# Support.net
KiCad netlist of a schematic drawn in Altium Designer
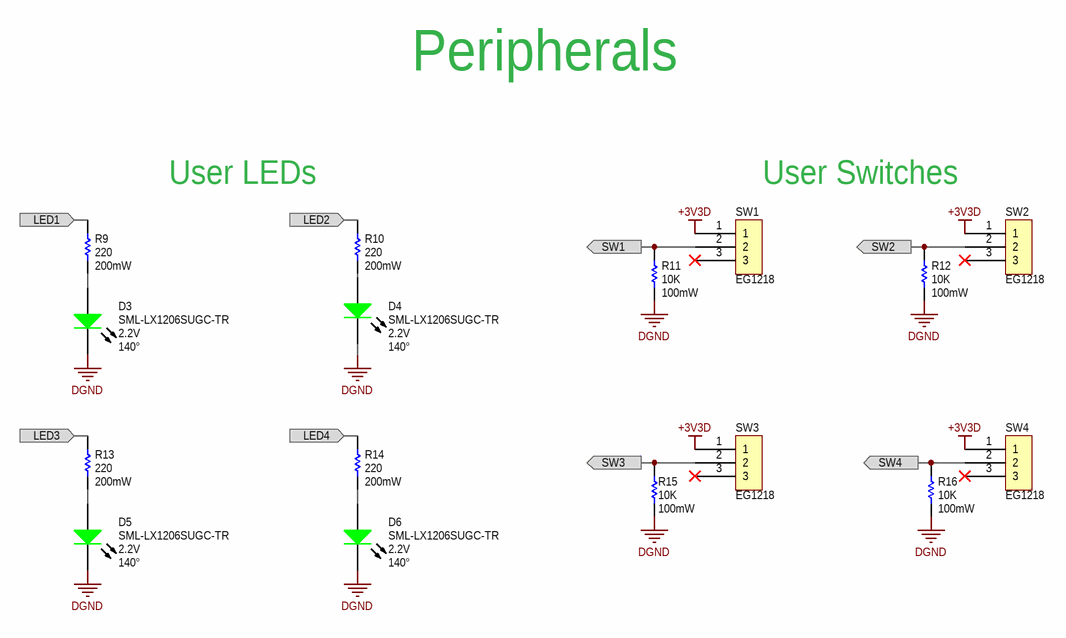
[diagram p0: Support.SchDoc]

(export (version "E")
  (design (tool "Eeschema 10.0.6"))
  (components
    (comp (ref "D3")
      (value "LED_GREEN 2")
      (footprint "DIOCP3216X11L")
      (description "LED ALINGAP ULT GRN CLR 1206 SMD")
      (fields
        (field (name "MANUFACTURER") "Lumex Opto/Components Inc")
        (field (name "MANUFACTURER PART NUMBER") "SML-LX1206SUGC-TR")
        (field (name "VOLTAGE - FORWARD (VF) TYP") "2.2V")
        (field (name "VIEWING ANGLE") "140°")
      )
      (libsource (lib "Schematic_Components") (part "LED_GREEN 2"))
    )
    (comp (ref "D4")
      (value "LED_GREEN 2")
      (footprint "DIOCP3216X11L")
      (description "LED ALINGAP ULT GRN CLR 1206 SMD")
      (fields
        (field (name "MANUFACTURER") "Lumex Opto/Components Inc")
        (field (name "MANUFACTURER PART NUMBER") "SML-LX1206SUGC-TR")
        (field (name "VOLTAGE - FORWARD (VF) TYP") "2.2V")
        (field (name "VIEWING ANGLE") "140°")
      )
      (libsource (lib "Schematic_Components") (part "LED_GREEN 2"))
    )
    (comp (ref "D5")
      (value "LED_GREEN 2")
      (footprint "DIOCP3216X11L")
      (description "LED ALINGAP ULT GRN CLR 1206 SMD")
      (fields
        (field (name "MANUFACTURER") "Lumex Opto/Components Inc")
        (field (name "MANUFACTURER PART NUMBER") "SML-LX1206SUGC-TR")
        (field (name "VOLTAGE - FORWARD (VF) TYP") "2.2V")
        (field (name "VIEWING ANGLE") "140°")
      )
      (libsource (lib "Schematic_Components") (part "LED_GREEN 2"))
    )
    (comp (ref "D6")
      (value "LED_GREEN 2")
      (footprint "DIOCP3216X11L")
      (description "LED ALINGAP ULT GRN CLR 1206 SMD")
      (fields
        (field (name "MANUFACTURER") "Lumex Opto/Components Inc")
        (field (name "MANUFACTURER PART NUMBER") "SML-LX1206SUGC-TR")
        (field (name "VOLTAGE - FORWARD (VF) TYP") "2.2V")
        (field (name "VIEWING ANGLE") "140°")
      )
      (libsource (lib "Schematic_Components") (part "LED_GREEN 2"))
    )
    (comp (ref "R9")
      (value "ERJ-PB3B2200V")
      (footprint "3-0603_R_L")
      (description "RES SMD 220 OHM 0.1% 1/5W 0603")
      (fields
        (field (name "MANUFACTURER") "Panasonic Electronic Components")
        (field (name "TOLERANCE") "±0.1%")
        (field (name "POWER (WATTS)") "200mW")
        (field (name "RESISTANCE (OHMS)") "220")
      )
      (libsource (lib "Schematic_Components_CD") (part "ERJ-PB3B2200V"))
    )
    (comp (ref "R10")
      (value "ERJ-PB3B2200V")
      (footprint "3-0603_R_L")
      (description "RES SMD 220 OHM 0.1% 1/5W 0603")
      (fields
        (field (name "MANUFACTURER") "Panasonic Electronic Components")
        (field (name "TOLERANCE") "±0.1%")
        (field (name "POWER (WATTS)") "200mW")
        (field (name "RESISTANCE (OHMS)") "220")
      )
      (libsource (lib "Schematic_Components_CD") (part "ERJ-PB3B2200V"))
    )
    (comp (ref "R11")
      (value "ERJ-3GEYJ103V")
      (footprint "3-0603_R_L")
      (description "RES 10K OHM 1/10W 5% 0603 SMD")
      (fields
        (field (name "MANUFACTURER") "Panasonic - ECG")
        (field (name "POWER (WATTS)") "100mW")
        (field (name "TOLERANCE") "±5%")
        (field (name "RESISTANCE (OHMS)") "10K")
      )
      (libsource (lib "Schematic_Components") (part "ERJ-3GEYJ103V"))
    )
    (comp (ref "R12")
      (value "ERJ-3GEYJ103V")
      (footprint "3-0603_R_L")
      (description "RES 10K OHM 1/10W 5% 0603 SMD")
      (fields
        (field (name "MANUFACTURER") "Panasonic - ECG")
        (field (name "POWER (WATTS)") "100mW")
        (field (name "TOLERANCE") "±5%")
        (field (name "RESISTANCE (OHMS)") "10K")
      )
      (libsource (lib "Schematic_Components") (part "ERJ-3GEYJ103V"))
    )
    (comp (ref "R13")
      (value "ERJ-PB3B2200V")
      (footprint "3-0603_R_L")
      (description "RES SMD 220 OHM 0.1% 1/5W 0603")
      (fields
        (field (name "MANUFACTURER") "Panasonic Electronic Components")
        (field (name "TOLERANCE") "±0.1%")
        (field (name "POWER (WATTS)") "200mW")
        (field (name "RESISTANCE (OHMS)") "220")
      )
      (libsource (lib "Schematic_Components_CD") (part "ERJ-PB3B2200V"))
    )
    (comp (ref "R14")
      (value "ERJ-PB3B2200V")
      (footprint "3-0603_R_L")
      (description "RES SMD 220 OHM 0.1% 1/5W 0603")
      (fields
        (field (name "MANUFACTURER") "Panasonic Electronic Components")
        (field (name "TOLERANCE") "±0.1%")
        (field (name "POWER (WATTS)") "200mW")
        (field (name "RESISTANCE (OHMS)") "220")
      )
      (libsource (lib "Schematic_Components_CD") (part "ERJ-PB3B2200V"))
    )
    (comp (ref "R15")
      (value "ERJ-3GEYJ103V")
      (footprint "3-0603_R_L")
      (description "RES 10K OHM 1/10W 5% 0603 SMD")
      (fields
        (field (name "MANUFACTURER") "Panasonic - ECG")
        (field (name "POWER (WATTS)") "100mW")
        (field (name "TOLERANCE") "±5%")
        (field (name "RESISTANCE (OHMS)") "10K")
      )
      (libsource (lib "Schematic_Components") (part "ERJ-3GEYJ103V"))
    )
    (comp (ref "R16")
      (value "ERJ-3GEYJ103V")
      (footprint "3-0603_R_L")
      (description "RES 10K OHM 1/10W 5% 0603 SMD")
      (fields
        (field (name "MANUFACTURER") "Panasonic - ECG")
        (field (name "POWER (WATTS)") "100mW")
        (field (name "TOLERANCE") "±5%")
        (field (name "RESISTANCE (OHMS)") "10K")
      )
      (libsource (lib "Schematic_Components") (part "ERJ-3GEYJ103V"))
    )
    (comp (ref "SW1")
      (value "Slide Switch SPDT Through Hole")
      (footprint "EG1218")
      (fields
        (field (name "MANUFACTURER") "E-Switch")
        (field (name "MANUFACTURER PART NUMBER") "EG1218")
        (field (name "PUBLISHER") "Altium Limited")
      )
      (libsource (lib "NIH_DE0_Nano_Daughter_Card_Library") (part "EG1218"))
    )
    (comp (ref "SW2")
      (value "Slide Switch SPDT Through Hole")
      (footprint "EG1218")
      (fields
        (field (name "MANUFACTURER") "E-Switch")
        (field (name "MANUFACTURER PART NUMBER") "EG1218")
        (field (name "PUBLISHER") "Altium Limited")
      )
      (libsource (lib "NIH_DE0_Nano_Daughter_Card_Library") (part "EG1218"))
    )
    (comp (ref "SW3")
      (value "Slide Switch SPDT Through Hole")
      (footprint "EG1218")
      (fields
        (field (name "MANUFACTURER") "E-Switch")
        (field (name "MANUFACTURER PART NUMBER") "EG1218")
        (field (name "PUBLISHER") "Altium Limited")
      )
      (libsource (lib "NIH_DE0_Nano_Daughter_Card_Library") (part "EG1218"))
    )
    (comp (ref "SW4")
      (value "Slide Switch SPDT Through Hole")
      (footprint "EG1218")
      (fields
        (field (name "MANUFACTURER") "E-Switch")
        (field (name "MANUFACTURER PART NUMBER") "EG1218")
        (field (name "PUBLISHER") "Altium Limited")
      )
      (libsource (lib "NIH_DE0_Nano_Daughter_Card_Library") (part "EG1218"))
    )
  )
  (nets
    (net (code "1") (name "+3V3D") (class "Default")
      (node (ref "SW1") (pin "1") (pinfunction "1_1") (pintype "passive"))
      (node (ref "SW2") (pin "1") (pinfunction "1_1") (pintype "passive"))
      (node (ref "SW3") (pin "1") (pinfunction "1_1") (pintype "passive"))
      (node (ref "SW4") (pin "1") (pinfunction "1_1") (pintype "passive"))
    )
    (net (code "2") (name "/LED1") (class "Default")
      (node (ref "R9") (pin "2") (pinfunction "2_2") (pintype "passive"))
    )
    (net (code "3") (name "/LED2") (class "Default")
      (node (ref "R10") (pin "2") (pinfunction "2_2") (pintype "passive"))
    )
    (net (code "4") (name "/LED3") (class "Default")
      (node (ref "R13") (pin "2") (pinfunction "2_2") (pintype "passive"))
    )
    (net (code "5") (name "/LED4") (class "Default")
      (node (ref "R14") (pin "2") (pinfunction "2_2") (pintype "passive"))
    )
    (net (code "6") (name "/SW1") (class "Default")
      (node (ref "R11") (pin "1") (pinfunction "1_1") (pintype "passive"))
      (node (ref "SW1") (pin "2") (pinfunction "2_2") (pintype "passive"))
    )
    (net (code "7") (name "/SW2") (class "Default")
      (node (ref "R12") (pin "1") (pinfunction "1_1") (pintype "passive"))
      (node (ref "SW2") (pin "2") (pinfunction "2_2") (pintype "passive"))
    )
    (net (code "8") (name "/SW3") (class "Default")
      (node (ref "R15") (pin "1") (pinfunction "1_1") (pintype "passive"))
      (node (ref "SW3") (pin "2") (pinfunction "2_2") (pintype "passive"))
    )
    (net (code "9") (name "/SW4") (class "Default")
      (node (ref "R16") (pin "1") (pinfunction "1_1") (pintype "passive"))
      (node (ref "SW4") (pin "2") (pinfunction "2_2") (pintype "passive"))
    )
    (net (code "10") (name "DGND") (class "Default")
      (node (ref "D3") (pin "2") (pinfunction "K_2") (pintype "passive"))
      (node (ref "D4") (pin "2") (pinfunction "K_2") (pintype "passive"))
      (node (ref "D5") (pin "2") (pinfunction "K_2") (pintype "passive"))
      (node (ref "D6") (pin "2") (pinfunction "K_2") (pintype "passive"))
      (node (ref "R11") (pin "2") (pinfunction "2_2") (pintype "passive"))
      (node (ref "R12") (pin "2") (pinfunction "2_2") (pintype "passive"))
      (node (ref "R15") (pin "2") (pinfunction "2_2") (pintype "passive"))
      (node (ref "R16") (pin "2") (pinfunction "2_2") (pintype "passive"))
    )
    (net (code "11") (name "Net-(D3-A)") (class "Default")
      (node (ref "D3") (pin "1") (pinfunction "A_1") (pintype "passive"))
      (node (ref "R9") (pin "1") (pinfunction "1_1") (pintype "passive"))
    )
    (net (code "12") (name "Net-(D4-A)") (class "Default")
      (node (ref "D4") (pin "1") (pinfunction "A_1") (pintype "passive"))
      (node (ref "R10") (pin "1") (pinfunction "1_1") (pintype "passive"))
    )
    (net (code "13") (name "Net-(D5-A)") (class "Default")
      (node (ref "D5") (pin "1") (pinfunction "A_1") (pintype "passive"))
      (node (ref "R13") (pin "1") (pinfunction "1_1") (pintype "passive"))
    )
    (net (code "14") (name "Net-(D6-A)") (class "Default")
      (node (ref "D6") (pin "1") (pinfunction "A_1") (pintype "passive"))
      (node (ref "R14") (pin "1") (pinfunction "1_1") (pintype "passive"))
    )
    (net (code "15") (name "unconnected-(SW1-Pad3)") (class "Default")
      (node (ref "SW1") (pin "3") (pinfunction "3_3") (pintype "passive+no_connect"))
    )
    (net (code "16") (name "unconnected-(SW2-Pad3)") (class "Default")
      (node (ref "SW2") (pin "3") (pinfunction "3_3") (pintype "passive+no_connect"))
    )
    (net (code "17") (name "unconnected-(SW3-Pad3)") (class "Default")
      (node (ref "SW3") (pin "3") (pinfunction "3_3") (pintype "passive+no_connect"))
    )
    (net (code "18") (name "unconnected-(SW4-Pad3)") (class "Default")
      (node (ref "SW4") (pin "3") (pinfunction "3_3") (pintype "passive+no_connect"))
    )
  )
)
